# BPF.net
KiCad netlist of a schematic drawn in Altium Designer
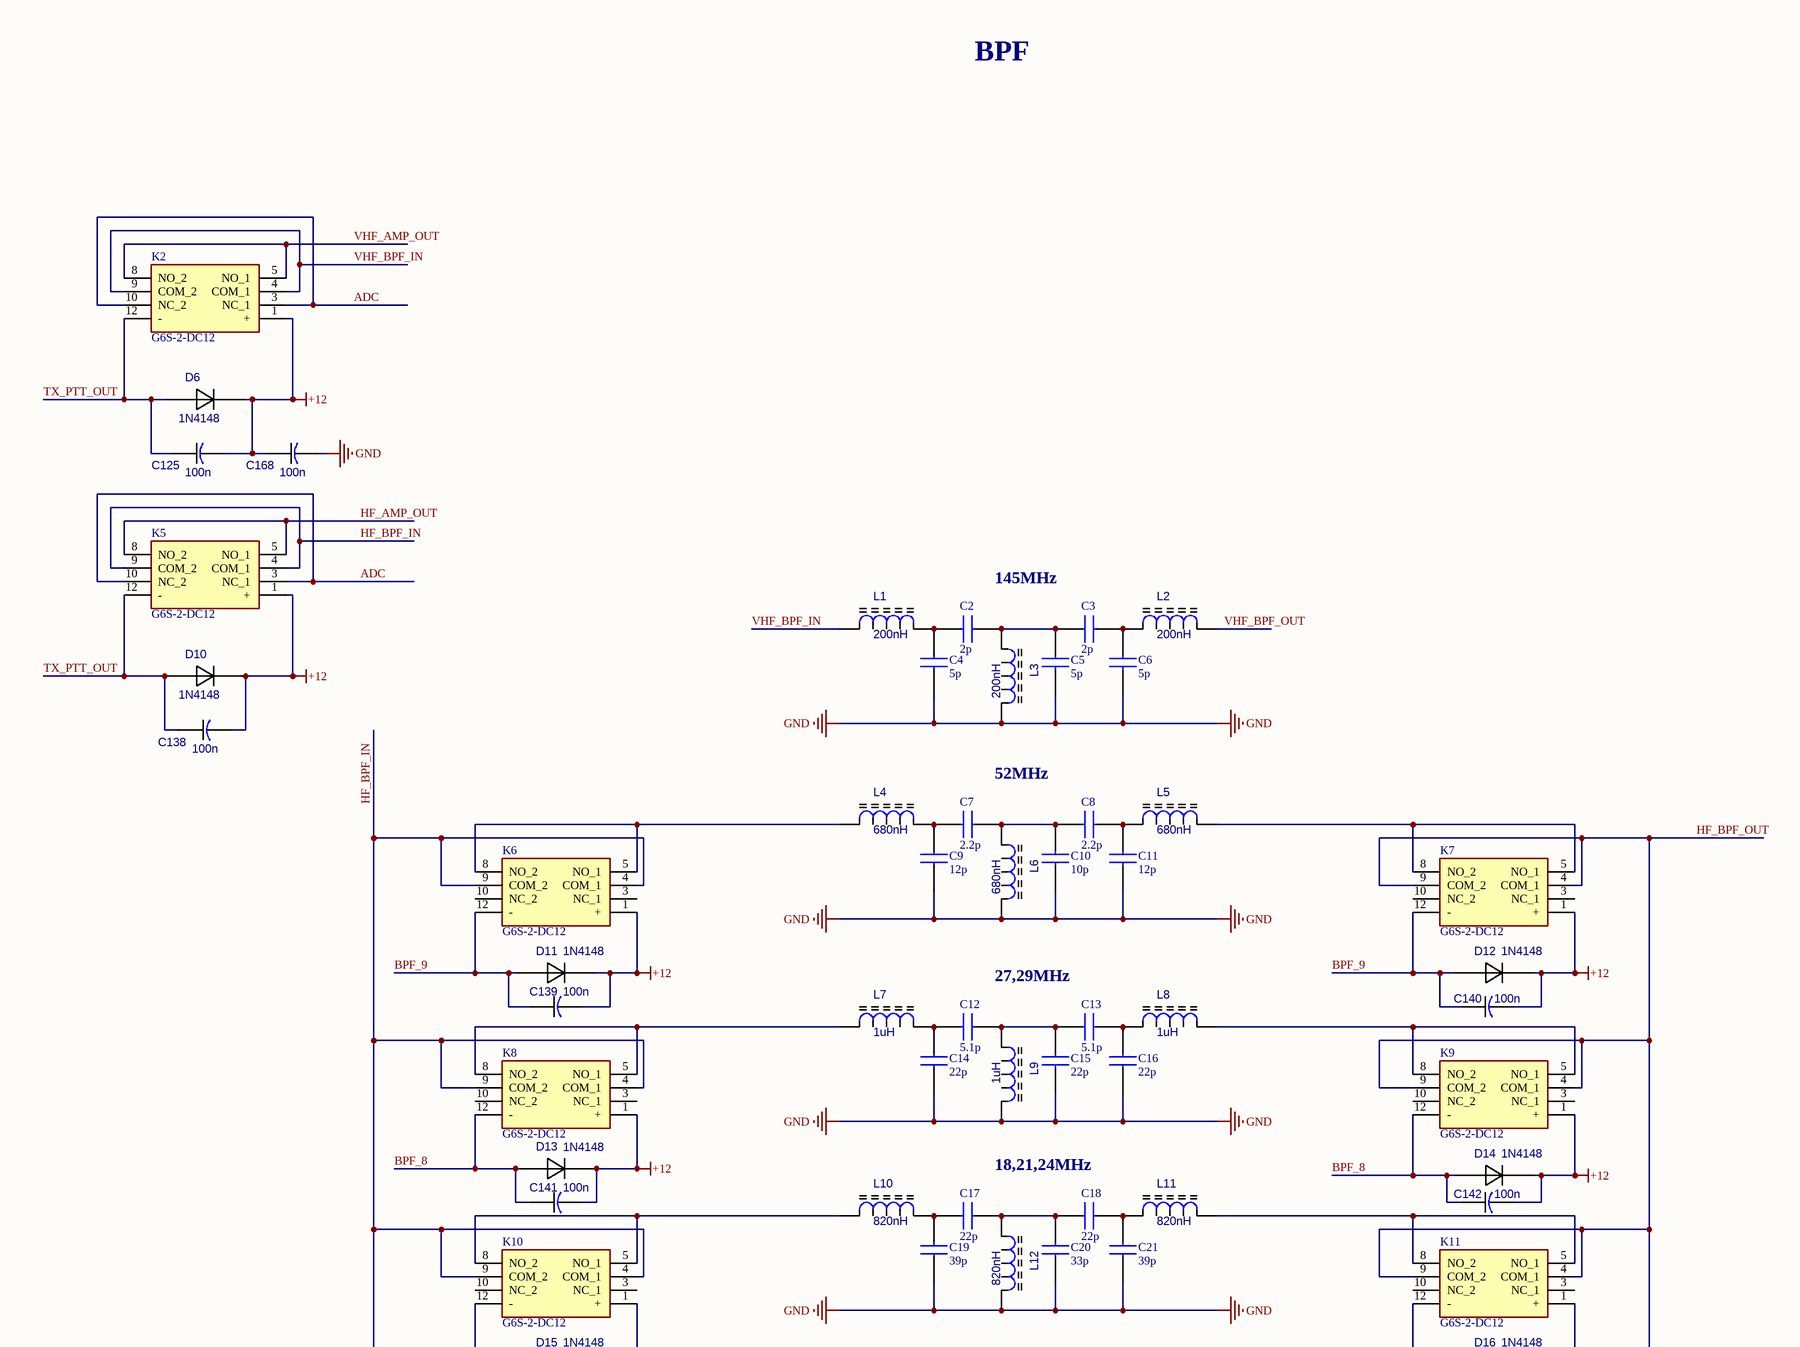
[diagram p0: BPF.SchDoc, top]
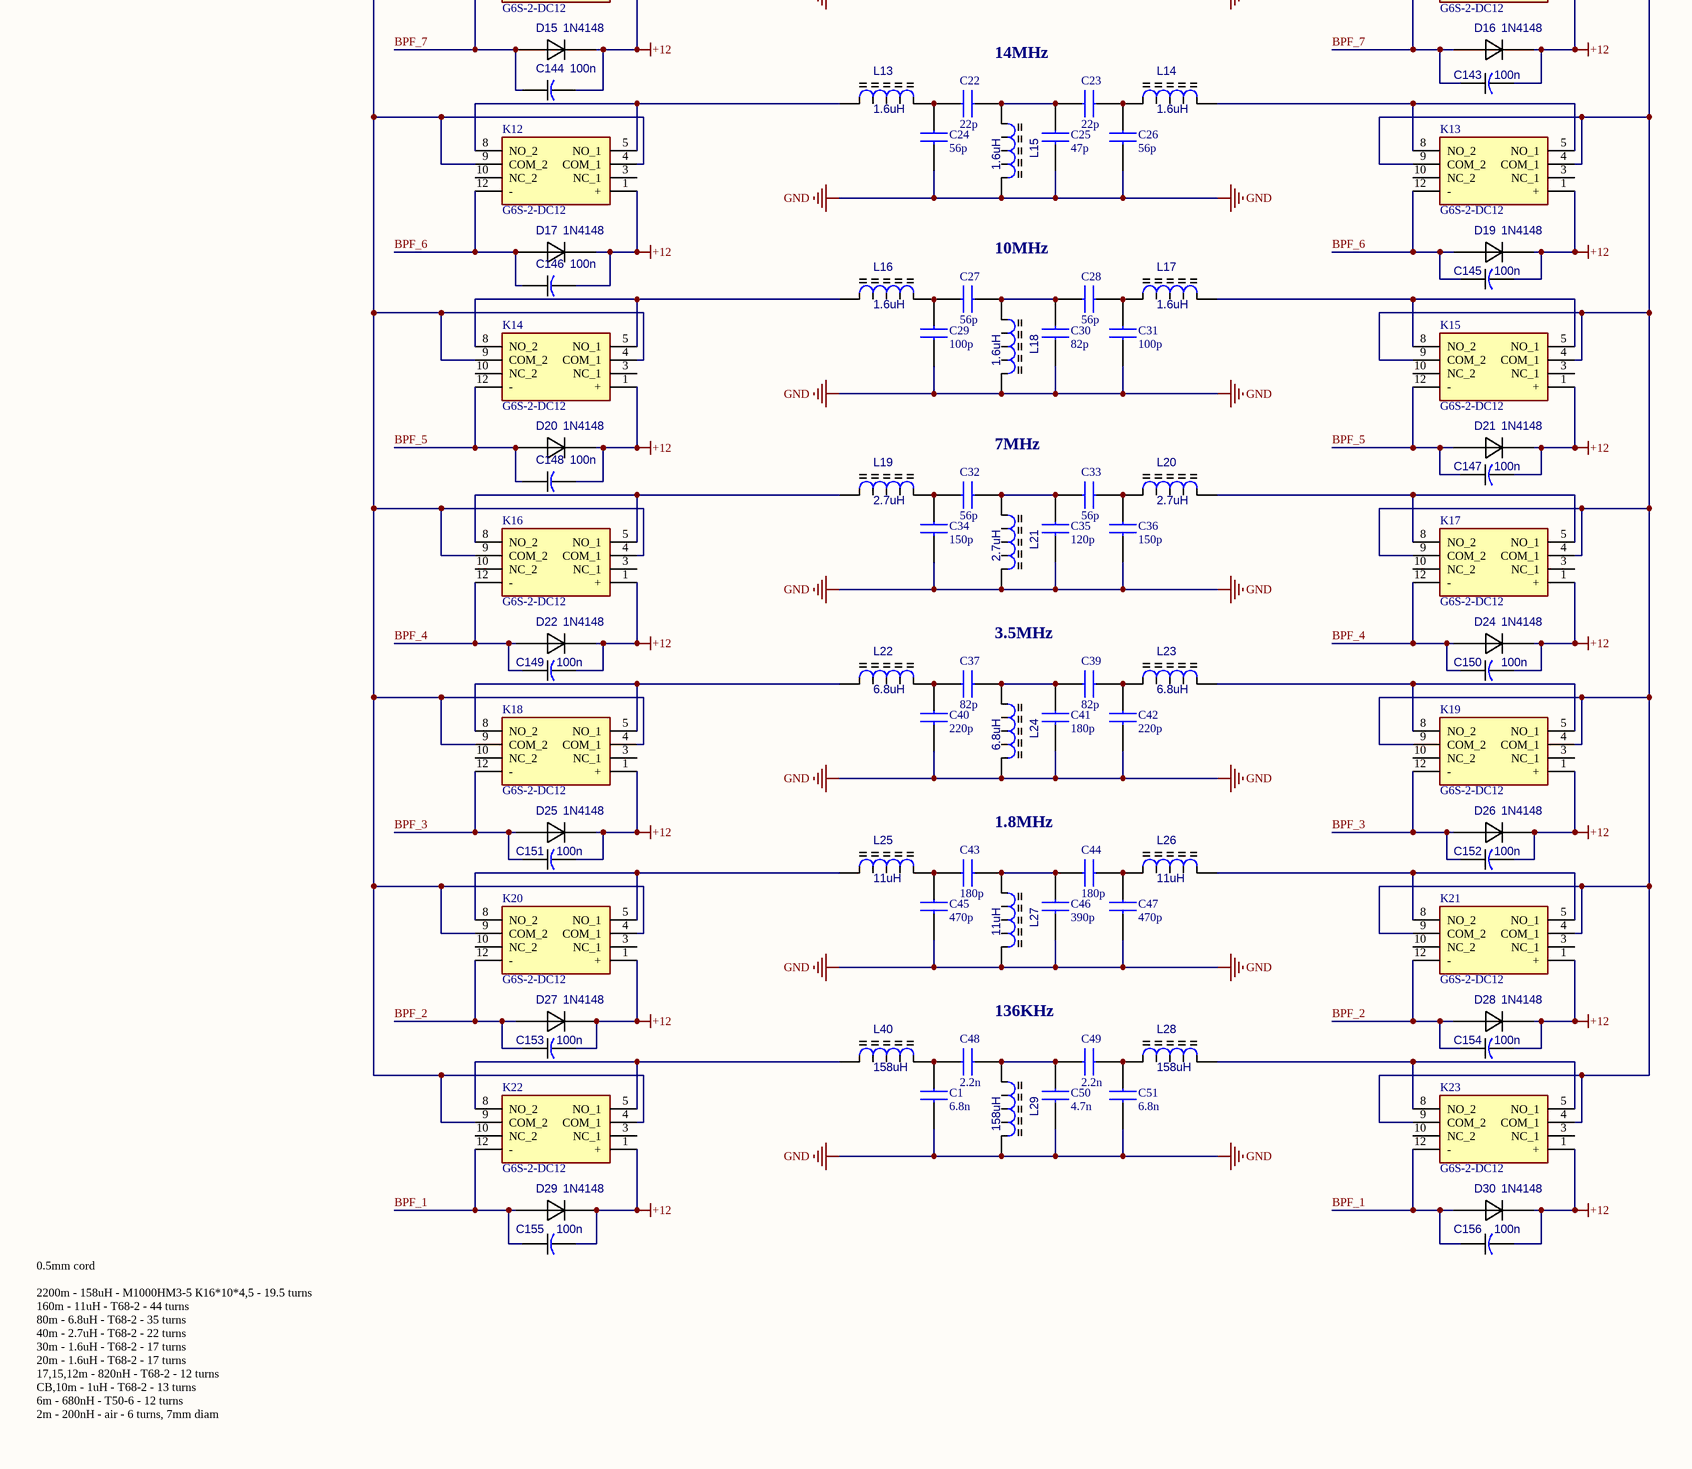
[diagram p1: BPF.SchDoc, bottom]

(export (version "E")
  (design (tool "Eeschema 10.0.6"))
  (components
    (comp (ref "C1")
      (value "6.8n")
      (footprint "CAP_1206")
      (description "Capacitor NP0 HiVolt")
      (fields
        (field (name "MANUFACTURER_PART_NUMBER") "B32620A0682J000")
        (field (name "MOUSER PART NUMBER") "871-B32620A682J")
      )
      (libsource (lib "*") (part "B32620A0682J000"))
    )
    (comp (ref "C2")
      (value "2p")
      (footprint "CAP_1206")
      (description "Capacitor NP0 HiVolt")
      (fields
        (field (name "MANUFACTURER_PART_NUMBER") "B32620A0682J000")
        (field (name "MOUSER PART NUMBER") "871-B32620A682J")
      )
      (libsource (lib "*") (part "B32620A0682J000"))
    )
    (comp (ref "C3")
      (value "2p")
      (footprint "CAP_1206")
      (description "Capacitor NP0 HiVolt")
      (fields
        (field (name "MANUFACTURER_PART_NUMBER") "B32620A0682J000")
        (field (name "MOUSER PART NUMBER") "871-B32620A682J")
      )
      (libsource (lib "*") (part "B32620A0682J000"))
    )
    (comp (ref "C4")
      (value "5p")
      (footprint "CAP_1206")
      (description "Capacitor NP0 HiVolt")
      (fields
        (field (name "MANUFACTURER_PART_NUMBER") "B32620A0682J000")
        (field (name "MOUSER PART NUMBER") "871-B32620A682J")
      )
      (libsource (lib "*") (part "B32620A0682J000"))
    )
    (comp (ref "C5")
      (value "5p")
      (footprint "CAP_1206")
      (description "Capacitor NP0 HiVolt")
      (fields
        (field (name "MANUFACTURER_PART_NUMBER") "B32620A0682J000")
        (field (name "MOUSER PART NUMBER") "871-B32620A682J")
      )
      (libsource (lib "*") (part "B32620A0682J000"))
    )
    (comp (ref "C6")
      (value "5p")
      (footprint "CAP_1206")
      (description "Capacitor NP0 HiVolt")
      (fields
        (field (name "MANUFACTURER_PART_NUMBER") "B32620A0682J000")
        (field (name "MOUSER PART NUMBER") "871-B32620A682J")
      )
      (libsource (lib "*") (part "B32620A0682J000"))
    )
    (comp (ref "C7")
      (value "2.2p")
      (footprint "CAP_1206")
      (description "Capacitor NP0 HiVolt")
      (fields
        (field (name "MANUFACTURER_PART_NUMBER") "B32620A0682J000")
        (field (name "MOUSER PART NUMBER") "871-B32620A682J")
      )
      (libsource (lib "*") (part "B32620A0682J000"))
    )
    (comp (ref "C8")
      (value "2.2p")
      (footprint "CAP_1206")
      (description "Capacitor NP0 HiVolt")
      (fields
        (field (name "MANUFACTURER_PART_NUMBER") "B32620A0682J000")
        (field (name "MOUSER PART NUMBER") "871-B32620A682J")
      )
      (libsource (lib "*") (part "B32620A0682J000"))
    )
    (comp (ref "C9")
      (value "12p")
      (footprint "CAP_1206")
      (description "Capacitor NP0 HiVolt")
      (fields
        (field (name "MANUFACTURER_PART_NUMBER") "B32620A0682J000")
        (field (name "MOUSER PART NUMBER") "871-B32620A682J")
      )
      (libsource (lib "*") (part "B32620A0682J000"))
    )
    (comp (ref "C10")
      (value "10p")
      (footprint "CAP_1206")
      (description "Capacitor NP0 HiVolt")
      (fields
        (field (name "MANUFACTURER_PART_NUMBER") "B32620A0682J000")
        (field (name "MOUSER PART NUMBER") "871-B32620A682J")
      )
      (libsource (lib "*") (part "B32620A0682J000"))
    )
    (comp (ref "C11")
      (value "12p")
      (footprint "CAP_1206")
      (description "Capacitor NP0 HiVolt")
      (fields
        (field (name "MANUFACTURER_PART_NUMBER") "B32620A0682J000")
        (field (name "MOUSER PART NUMBER") "871-B32620A682J")
      )
      (libsource (lib "*") (part "B32620A0682J000"))
    )
    (comp (ref "C12")
      (value "5.1p")
      (footprint "CAP_1206")
      (description "Capacitor NP0 HiVolt")
      (fields
        (field (name "MANUFACTURER_PART_NUMBER") "B32620A0682J000")
        (field (name "MOUSER PART NUMBER") "871-B32620A682J")
      )
      (libsource (lib "*") (part "B32620A0682J000"))
    )
    (comp (ref "C13")
      (value "5.1p")
      (footprint "CAP_1206")
      (description "Capacitor NP0 HiVolt")
      (fields
        (field (name "MANUFACTURER_PART_NUMBER") "B32620A0682J000")
        (field (name "MOUSER PART NUMBER") "871-B32620A682J")
      )
      (libsource (lib "*") (part "B32620A0682J000"))
    )
    (comp (ref "C14")
      (value "22p")
      (footprint "CAP_1206")
      (description "Capacitor NP0 HiVolt")
      (fields
        (field (name "MANUFACTURER_PART_NUMBER") "B32620A0682J000")
        (field (name "MOUSER PART NUMBER") "871-B32620A682J")
      )
      (libsource (lib "*") (part "B32620A0682J000"))
    )
    (comp (ref "C15")
      (value "22p")
      (footprint "CAP_1206")
      (description "Capacitor NP0 HiVolt")
      (fields
        (field (name "MANUFACTURER_PART_NUMBER") "B32620A0682J000")
        (field (name "MOUSER PART NUMBER") "871-B32620A682J")
      )
      (libsource (lib "*") (part "B32620A0682J000"))
    )
    (comp (ref "C16")
      (value "22p")
      (footprint "CAP_1206")
      (description "Capacitor NP0 HiVolt")
      (fields
        (field (name "MANUFACTURER_PART_NUMBER") "B32620A0682J000")
        (field (name "MOUSER PART NUMBER") "871-B32620A682J")
      )
      (libsource (lib "*") (part "B32620A0682J000"))
    )
    (comp (ref "C17")
      (value "22p")
      (footprint "CAP_1206")
      (description "Capacitor NP0 HiVolt")
      (fields
        (field (name "MANUFACTURER_PART_NUMBER") "B32620A0682J000")
        (field (name "MOUSER PART NUMBER") "871-B32620A682J")
      )
      (libsource (lib "*") (part "B32620A0682J000"))
    )
    (comp (ref "C18")
      (value "22p")
      (footprint "CAP_1206")
      (description "Capacitor NP0 HiVolt")
      (fields
        (field (name "MANUFACTURER_PART_NUMBER") "B32620A0682J000")
        (field (name "MOUSER PART NUMBER") "871-B32620A682J")
      )
      (libsource (lib "*") (part "B32620A0682J000"))
    )
    (comp (ref "C19")
      (value "39p")
      (footprint "CAP_1206")
      (description "Capacitor NP0 HiVolt")
      (fields
        (field (name "MANUFACTURER_PART_NUMBER") "B32620A0682J000")
        (field (name "MOUSER PART NUMBER") "871-B32620A682J")
      )
      (libsource (lib "*") (part "B32620A0682J000"))
    )
    (comp (ref "C20")
      (value "33p")
      (footprint "CAP_1206")
      (description "Capacitor NP0 HiVolt")
      (fields
        (field (name "MANUFACTURER_PART_NUMBER") "B32620A0682J000")
        (field (name "MOUSER PART NUMBER") "871-B32620A682J")
      )
      (libsource (lib "*") (part "B32620A0682J000"))
    )
    (comp (ref "C21")
      (value "39p")
      (footprint "CAP_1206")
      (description "Capacitor NP0 HiVolt")
      (fields
        (field (name "MANUFACTURER_PART_NUMBER") "B32620A0682J000")
        (field (name "MOUSER PART NUMBER") "871-B32620A682J")
      )
      (libsource (lib "*") (part "B32620A0682J000"))
    )
    (comp (ref "C22")
      (value "22p")
      (footprint "CAP_1206")
      (description "Capacitor NP0 HiVolt")
      (fields
        (field (name "MANUFACTURER_PART_NUMBER") "B32620A0682J000")
        (field (name "MOUSER PART NUMBER") "871-B32620A682J")
      )
      (libsource (lib "*") (part "B32620A0682J000"))
    )
    (comp (ref "C23")
      (value "22p")
      (footprint "CAP_1206")
      (description "Capacitor NP0 HiVolt")
      (fields
        (field (name "MANUFACTURER_PART_NUMBER") "B32620A0682J000")
        (field (name "MOUSER PART NUMBER") "871-B32620A682J")
      )
      (libsource (lib "*") (part "B32620A0682J000"))
    )
    (comp (ref "C24")
      (value "56p")
      (footprint "CAP_1206")
      (description "Capacitor NP0 HiVolt")
      (fields
        (field (name "MANUFACTURER_PART_NUMBER") "B32620A0682J000")
        (field (name "MOUSER PART NUMBER") "871-B32620A682J")
      )
      (libsource (lib "*") (part "B32620A0682J000"))
    )
    (comp (ref "C25")
      (value "47p")
      (footprint "CAP_1206")
      (description "Capacitor NP0 HiVolt")
      (fields
        (field (name "MANUFACTURER_PART_NUMBER") "B32620A0682J000")
        (field (name "MOUSER PART NUMBER") "871-B32620A682J")
      )
      (libsource (lib "*") (part "B32620A0682J000"))
    )
    (comp (ref "C26")
      (value "56p")
      (footprint "CAP_1206")
      (description "Capacitor NP0 HiVolt")
      (fields
        (field (name "MANUFACTURER_PART_NUMBER") "B32620A0682J000")
        (field (name "MOUSER PART NUMBER") "871-B32620A682J")
      )
      (libsource (lib "*") (part "B32620A0682J000"))
    )
    (comp (ref "C27")
      (value "56p")
      (footprint "CAP_1206")
      (description "Capacitor NP0 HiVolt")
      (fields
        (field (name "MANUFACTURER_PART_NUMBER") "B32620A0682J000")
        (field (name "MOUSER PART NUMBER") "871-B32620A682J")
      )
      (libsource (lib "*") (part "B32620A0682J000"))
    )
    (comp (ref "C28")
      (value "56p")
      (footprint "CAP_1206")
      (description "Capacitor NP0 HiVolt")
      (fields
        (field (name "MANUFACTURER_PART_NUMBER") "B32620A0682J000")
        (field (name "MOUSER PART NUMBER") "871-B32620A682J")
      )
      (libsource (lib "*") (part "B32620A0682J000"))
    )
    (comp (ref "C29")
      (value "100p")
      (footprint "CAP_1206")
      (description "Capacitor NP0 HiVolt")
      (fields
        (field (name "MANUFACTURER_PART_NUMBER") "B32620A0682J000")
        (field (name "MOUSER PART NUMBER") "871-B32620A682J")
      )
      (libsource (lib "*") (part "B32620A0682J000"))
    )
    (comp (ref "C30")
      (value "82p")
      (footprint "CAP_1206")
      (description "Capacitor NP0 HiVolt")
      (fields
        (field (name "MANUFACTURER_PART_NUMBER") "B32620A0682J000")
        (field (name "MOUSER PART NUMBER") "871-B32620A682J")
      )
      (libsource (lib "*") (part "B32620A0682J000"))
    )
    (comp (ref "C31")
      (value "100p")
      (footprint "CAP_1206")
      (description "Capacitor NP0 HiVolt")
      (fields
        (field (name "MANUFACTURER_PART_NUMBER") "B32620A0682J000")
        (field (name "MOUSER PART NUMBER") "871-B32620A682J")
      )
      (libsource (lib "*") (part "B32620A0682J000"))
    )
    (comp (ref "C32")
      (value "56p")
      (footprint "CAP_1206")
      (description "Capacitor NP0 HiVolt")
      (fields
        (field (name "MANUFACTURER_PART_NUMBER") "B32620A0682J000")
        (field (name "MOUSER PART NUMBER") "871-B32620A682J")
      )
      (libsource (lib "*") (part "B32620A0682J000"))
    )
    (comp (ref "C33")
      (value "56p")
      (footprint "CAP_1206")
      (description "Capacitor NP0 HiVolt")
      (fields
        (field (name "MANUFACTURER_PART_NUMBER") "B32620A0682J000")
        (field (name "MOUSER PART NUMBER") "871-B32620A682J")
      )
      (libsource (lib "*") (part "B32620A0682J000"))
    )
    (comp (ref "C34")
      (value "150p")
      (footprint "CAP_1206")
      (description "Capacitor NP0 HiVolt")
      (fields
        (field (name "MANUFACTURER_PART_NUMBER") "B32620A0682J000")
        (field (name "MOUSER PART NUMBER") "871-B32620A682J")
      )
      (libsource (lib "*") (part "B32620A0682J000"))
    )
    (comp (ref "C35")
      (value "120p")
      (footprint "CAP_1206")
      (description "Capacitor NP0 HiVolt")
      (fields
        (field (name "MANUFACTURER_PART_NUMBER") "B32620A0682J000")
        (field (name "MOUSER PART NUMBER") "871-B32620A682J")
      )
      (libsource (lib "*") (part "B32620A0682J000"))
    )
    (comp (ref "C36")
      (value "150p")
      (footprint "CAP_1206")
      (description "Capacitor NP0 HiVolt")
      (fields
        (field (name "MANUFACTURER_PART_NUMBER") "B32620A0682J000")
        (field (name "MOUSER PART NUMBER") "871-B32620A682J")
      )
      (libsource (lib "*") (part "B32620A0682J000"))
    )
    (comp (ref "C37")
      (value "82p")
      (footprint "CAP_1206")
      (description "Capacitor NP0 HiVolt")
      (fields
        (field (name "MANUFACTURER_PART_NUMBER") "B32620A0682J000")
        (field (name "MOUSER PART NUMBER") "871-B32620A682J")
      )
      (libsource (lib "*") (part "B32620A0682J000"))
    )
    (comp (ref "C39")
      (value "82p")
      (footprint "CAP_1206")
      (description "Capacitor NP0 HiVolt")
      (fields
        (field (name "MANUFACTURER_PART_NUMBER") "B32620A0682J000")
        (field (name "MOUSER PART NUMBER") "871-B32620A682J")
      )
      (libsource (lib "*") (part "B32620A0682J000"))
    )
    (comp (ref "C40")
      (value "220p")
      (footprint "CAP_1206")
      (description "Capacitor NP0 HiVolt")
      (fields
        (field (name "MANUFACTURER_PART_NUMBER") "B32620A0682J000")
        (field (name "MOUSER PART NUMBER") "871-B32620A682J")
      )
      (libsource (lib "*") (part "B32620A0682J000"))
    )
    (comp (ref "C41")
      (value "180p")
      (footprint "CAP_1206")
      (description "Capacitor NP0 HiVolt")
      (fields
        (field (name "MANUFACTURER_PART_NUMBER") "B32620A0682J000")
        (field (name "MOUSER PART NUMBER") "871-B32620A682J")
      )
      (libsource (lib "*") (part "B32620A0682J000"))
    )
    (comp (ref "C42")
      (value "220p")
      (footprint "CAP_1206")
      (description "Capacitor NP0 HiVolt")
      (fields
        (field (name "MANUFACTURER_PART_NUMBER") "B32620A0682J000")
        (field (name "MOUSER PART NUMBER") "871-B32620A682J")
      )
      (libsource (lib "*") (part "B32620A0682J000"))
    )
    (comp (ref "C43")
      (value "180p")
      (footprint "CAP_1206")
      (description "Capacitor NP0 HiVolt")
      (fields
        (field (name "MANUFACTURER_PART_NUMBER") "B32620A0682J000")
        (field (name "MOUSER PART NUMBER") "871-B32620A682J")
      )
      (libsource (lib "*") (part "B32620A0682J000"))
    )
    (comp (ref "C44")
      (value "180p")
      (footprint "CAP_1206")
      (description "Capacitor NP0 HiVolt")
      (fields
        (field (name "MANUFACTURER_PART_NUMBER") "B32620A0682J000")
        (field (name "MOUSER PART NUMBER") "871-B32620A682J")
      )
      (libsource (lib "*") (part "B32620A0682J000"))
    )
    (comp (ref "C45")
      (value "470p")
      (footprint "CAP_1206")
      (description "Capacitor NP0 HiVolt")
      (fields
        (field (name "MANUFACTURER_PART_NUMBER") "B32620A0682J000")
        (field (name "MOUSER PART NUMBER") "871-B32620A682J")
      )
      (libsource (lib "*") (part "B32620A0682J000"))
    )
    (comp (ref "C46")
      (value "390p")
      (footprint "CAP_1206")
      (description "Capacitor NP0 HiVolt")
      (fields
        (field (name "MANUFACTURER_PART_NUMBER") "B32620A0682J000")
        (field (name "MOUSER PART NUMBER") "871-B32620A682J")
      )
      (libsource (lib "*") (part "B32620A0682J000"))
    )
    (comp (ref "C47")
      (value "470p")
      (footprint "CAP_1206")
      (description "Capacitor NP0 HiVolt")
      (fields
        (field (name "MANUFACTURER_PART_NUMBER") "B32620A0682J000")
        (field (name "MOUSER PART NUMBER") "871-B32620A682J")
      )
      (libsource (lib "*") (part "B32620A0682J000"))
    )
    (comp (ref "C48")
      (value "2.2n")
      (footprint "CAP_1206")
      (description "Capacitor NP0 HiVolt")
      (fields
        (field (name "MANUFACTURER_PART_NUMBER") "B32620A0682J000")
        (field (name "MOUSER PART NUMBER") "871-B32620A682J")
      )
      (libsource (lib "*") (part "B32620A0682J000"))
    )
    (comp (ref "C49")
      (value "2.2n")
      (footprint "CAP_1206")
      (description "Capacitor NP0 HiVolt")
      (fields
        (field (name "MANUFACTURER_PART_NUMBER") "B32620A0682J000")
        (field (name "MOUSER PART NUMBER") "871-B32620A682J")
      )
      (libsource (lib "*") (part "B32620A0682J000"))
    )
    (comp (ref "C50")
      (value "4.7n")
      (footprint "CAP_1206")
      (description "Capacitor NP0 HiVolt")
      (fields
        (field (name "MANUFACTURER_PART_NUMBER") "B32620A0682J000")
        (field (name "MOUSER PART NUMBER") "871-B32620A682J")
      )
      (libsource (lib "*") (part "B32620A0682J000"))
    )
    (comp (ref "C51")
      (value "6.8n")
      (footprint "CAP_1206")
      (description "Capacitor NP0 HiVolt")
      (fields
        (field (name "MANUFACTURER_PART_NUMBER") "B32620A0682J000")
        (field (name "MOUSER PART NUMBER") "871-B32620A682J")
      )
      (libsource (lib "*") (part "B32620A0682J000"))
    )
    (comp (ref "C125")
      (value "100n")
      (footprint "CAP_0805")
      (description "CAP_0805")
      (libsource (lib "*") (part "CAP_0805"))
    )
    (comp (ref "C138")
      (value "100n")
      (footprint "CAP_0805")
      (description "CAP_0805")
      (libsource (lib "*") (part "CAP_0805"))
    )
    (comp (ref "C139")
      (value "100n")
      (footprint "CAP_0805")
      (description "CAP_0805")
      (libsource (lib "*") (part "CAP_0805"))
    )
    (comp (ref "C140")
      (value "100n")
      (footprint "CAP_0805")
      (description "CAP_0805")
      (libsource (lib "*") (part "CAP_0805"))
    )
    (comp (ref "C141")
      (value "100n")
      (footprint "CAP_0805")
      (description "CAP_0805")
      (libsource (lib "*") (part "CAP_0805"))
    )
    (comp (ref "C142")
      (value "100n")
      (footprint "CAP_0805")
      (description "CAP_0805")
      (libsource (lib "*") (part "CAP_0805"))
    )
    (comp (ref "C143")
      (value "100n")
      (footprint "CAP_0805")
      (description "CAP_0805")
      (libsource (lib "*") (part "CAP_0805"))
    )
    (comp (ref "C144")
      (value "100n")
      (footprint "CAP_0805")
      (description "CAP_0805")
      (libsource (lib "*") (part "CAP_0805"))
    )
    (comp (ref "C145")
      (value "100n")
      (footprint "CAP_0805")
      (description "CAP_0805")
      (libsource (lib "*") (part "CAP_0805"))
    )
    (comp (ref "C146")
      (value "100n")
      (footprint "CAP_0805")
      (description "CAP_0805")
      (libsource (lib "*") (part "CAP_0805"))
    )
    (comp (ref "C147")
      (value "100n")
      (footprint "CAP_0805")
      (description "CAP_0805")
      (libsource (lib "*") (part "CAP_0805"))
    )
    (comp (ref "C148")
      (value "100n")
      (footprint "CAP_0805")
      (description "CAP_0805")
      (libsource (lib "*") (part "CAP_0805"))
    )
    (comp (ref "C149")
      (value "100n")
      (footprint "CAP_0805")
      (description "CAP_0805")
      (libsource (lib "*") (part "CAP_0805"))
    )
    (comp (ref "C150")
      (value "100n")
      (footprint "CAP_0805")
      (description "CAP_0805")
      (libsource (lib "*") (part "CAP_0805"))
    )
    (comp (ref "C151")
      (value "100n")
      (footprint "CAP_0805")
      (description "CAP_0805")
      (libsource (lib "*") (part "CAP_0805"))
    )
    (comp (ref "C152")
      (value "100n")
      (footprint "CAP_0805")
      (description "CAP_0805")
      (libsource (lib "*") (part "CAP_0805"))
    )
    (comp (ref "C153")
      (value "100n")
      (footprint "CAP_0805")
      (description "CAP_0805")
      (libsource (lib "*") (part "CAP_0805"))
    )
    (comp (ref "C154")
      (value "100n")
      (footprint "CAP_0805")
      (description "CAP_0805")
      (libsource (lib "*") (part "CAP_0805"))
    )
    (comp (ref "C155")
      (value "100n")
      (footprint "CAP_0805")
      (description "CAP_0805")
      (libsource (lib "*") (part "CAP_0805"))
    )
    (comp (ref "C156")
      (value "100n")
      (footprint "CAP_0805")
      (description "CAP_0805")
      (libsource (lib "*") (part "CAP_0805"))
    )
    (comp (ref "C168")
      (value "100n")
      (footprint "CAP_0805")
      (description "CAP_0805")
      (libsource (lib "*") (part "CAP_0805"))
    )
    (comp (ref "D6") (value "1N4148") (footprint "SS14") (libsource (lib "RF-UNIT-BIG") (part "1N4148")))
    (comp (ref "D10") (value "1N4148") (footprint "SS14") (libsource (lib "RF-UNIT-BIG") (part "1N4148")))
    (comp (ref "D11") (value "1N4148") (footprint "SS14") (libsource (lib "RF-UNIT-BIG") (part "1N4148")))
    (comp (ref "D12") (value "1N4148") (footprint "SS14") (libsource (lib "RF-UNIT-BIG") (part "1N4148")))
    (comp (ref "D13") (value "1N4148") (footprint "SS14") (libsource (lib "RF-UNIT-BIG") (part "1N4148")))
    (comp (ref "D14") (value "1N4148") (footprint "SS14") (libsource (lib "RF-UNIT-BIG") (part "1N4148")))
    (comp (ref "D15") (value "1N4148") (footprint "SS14") (libsource (lib "RF-UNIT-BIG") (part "1N4148")))
    (comp (ref "D16") (value "1N4148") (footprint "SS14") (libsource (lib "RF-UNIT-BIG") (part "1N4148")))
    (comp (ref "D17") (value "1N4148") (footprint "SS14") (libsource (lib "RF-UNIT-BIG") (part "1N4148")))
    (comp (ref "D19") (value "1N4148") (footprint "SS14") (libsource (lib "RF-UNIT-BIG") (part "1N4148")))
    (comp (ref "D20") (value "1N4148") (footprint "SS14") (libsource (lib "RF-UNIT-BIG") (part "1N4148")))
    (comp (ref "D21") (value "1N4148") (footprint "SS14") (libsource (lib "RF-UNIT-BIG") (part "1N4148")))
    (comp (ref "D22") (value "1N4148") (footprint "SS14") (libsource (lib "RF-UNIT-BIG") (part "1N4148")))
    (comp (ref "D24") (value "1N4148") (footprint "SS14") (libsource (lib "RF-UNIT-BIG") (part "1N4148")))
    (comp (ref "D25") (value "1N4148") (footprint "SS14") (libsource (lib "RF-UNIT-BIG") (part "1N4148")))
    (comp (ref "D26") (value "1N4148") (footprint "SS14") (libsource (lib "RF-UNIT-BIG") (part "1N4148")))
    (comp (ref "D27") (value "1N4148") (footprint "SS14") (libsource (lib "RF-UNIT-BIG") (part "1N4148")))
    (comp (ref "D28") (value "1N4148") (footprint "SS14") (libsource (lib "RF-UNIT-BIG") (part "1N4148")))
    (comp (ref "D29") (value "1N4148") (footprint "SS14") (libsource (lib "RF-UNIT-BIG") (part "1N4148")))
    (comp (ref "D30") (value "1N4148") (footprint "SS14") (libsource (lib "RF-UNIT-BIG") (part "1N4148")))
    (comp (ref "K2")
      (value "G6S-2-DC12")
      (footprint "SamacSys:G6S2DC12")
      (description "Relay or Contactor")
      (fields (field (name "MOUSER PART NUMBER") "653-G6S-2-DC12A"))
      (libsource (lib "*") (part "G6S-2-DC12"))
    )
    (comp (ref "K5")
      (value "G6S-2-DC12")
      (footprint "SamacSys:G6S2DC12")
      (description "Relay or Contactor")
      (fields (field (name "MOUSER PART NUMBER") "653-G6S-2-DC12A"))
      (libsource (lib "*") (part "G6S-2-DC12"))
    )
    (comp (ref "K6")
      (value "G6S-2-DC12")
      (footprint "SamacSys:G6S2DC12")
      (description "Relay or Contactor")
      (fields (field (name "MOUSER PART NUMBER") "653-G6S-2-DC12A"))
      (libsource (lib "*") (part "G6S-2-DC12"))
    )
    (comp (ref "K7")
      (value "G6S-2-DC12")
      (footprint "SamacSys:G6S2DC12")
      (description "Relay or Contactor")
      (fields (field (name "MOUSER PART NUMBER") "653-G6S-2-DC12A"))
      (libsource (lib "*") (part "G6S-2-DC12"))
    )
    (comp (ref "K8")
      (value "G6S-2-DC12")
      (footprint "SamacSys:G6S2DC12")
      (description "Relay or Contactor")
      (fields (field (name "MOUSER PART NUMBER") "653-G6S-2-DC12A"))
      (libsource (lib "*") (part "G6S-2-DC12"))
    )
    (comp (ref "K9")
      (value "G6S-2-DC12")
      (footprint "SamacSys:G6S2DC12")
      (description "Relay or Contactor")
      (fields (field (name "MOUSER PART NUMBER") "653-G6S-2-DC12A"))
      (libsource (lib "*") (part "G6S-2-DC12"))
    )
    (comp (ref "K10")
      (value "G6S-2-DC12")
      (footprint "SamacSys:G6S2DC12")
      (description "Relay or Contactor")
      (fields (field (name "MOUSER PART NUMBER") "653-G6S-2-DC12A"))
      (libsource (lib "*") (part "G6S-2-DC12"))
    )
    (comp (ref "K11")
      (value "G6S-2-DC12")
      (footprint "SamacSys:G6S2DC12")
      (description "Relay or Contactor")
      (fields (field (name "MOUSER PART NUMBER") "653-G6S-2-DC12A"))
      (libsource (lib "*") (part "G6S-2-DC12"))
    )
    (comp (ref "K12")
      (value "G6S-2-DC12")
      (footprint "SamacSys:G6S2DC12")
      (description "Relay or Contactor")
      (fields (field (name "MOUSER PART NUMBER") "653-G6S-2-DC12A"))
      (libsource (lib "*") (part "G6S-2-DC12"))
    )
    (comp (ref "K13")
      (value "G6S-2-DC12")
      (footprint "SamacSys:G6S2DC12")
      (description "Relay or Contactor")
      (fields (field (name "MOUSER PART NUMBER") "653-G6S-2-DC12A"))
      (libsource (lib "*") (part "G6S-2-DC12"))
    )
    (comp (ref "K14")
      (value "G6S-2-DC12")
      (footprint "SamacSys:G6S2DC12")
      (description "Relay or Contactor")
      (fields (field (name "MOUSER PART NUMBER") "653-G6S-2-DC12A"))
      (libsource (lib "*") (part "G6S-2-DC12"))
    )
    (comp (ref "K15")
      (value "G6S-2-DC12")
      (footprint "SamacSys:G6S2DC12")
      (description "Relay or Contactor")
      (fields (field (name "MOUSER PART NUMBER") "653-G6S-2-DC12A"))
      (libsource (lib "*") (part "G6S-2-DC12"))
    )
    (comp (ref "K16")
      (value "G6S-2-DC12")
      (footprint "SamacSys:G6S2DC12")
      (description "Relay or Contactor")
      (fields (field (name "MOUSER PART NUMBER") "653-G6S-2-DC12A"))
      (libsource (lib "*") (part "G6S-2-DC12"))
    )
    (comp (ref "K17")
      (value "G6S-2-DC12")
      (footprint "SamacSys:G6S2DC12")
      (description "Relay or Contactor")
      (fields (field (name "MOUSER PART NUMBER") "653-G6S-2-DC12A"))
      (libsource (lib "*") (part "G6S-2-DC12"))
    )
    (comp (ref "K18")
      (value "G6S-2-DC12")
      (footprint "SamacSys:G6S2DC12")
      (description "Relay or Contactor")
      (fields (field (name "MOUSER PART NUMBER") "653-G6S-2-DC12A"))
      (libsource (lib "*") (part "G6S-2-DC12"))
    )
    (comp (ref "K19")
      (value "G6S-2-DC12")
      (footprint "SamacSys:G6S2DC12")
      (description "Relay or Contactor")
      (fields (field (name "MOUSER PART NUMBER") "653-G6S-2-DC12A"))
      (libsource (lib "*") (part "G6S-2-DC12"))
    )
    (comp (ref "K20")
      (value "G6S-2-DC12")
      (footprint "SamacSys:G6S2DC12")
      (description "Relay or Contactor")
      (fields (field (name "MOUSER PART NUMBER") "653-G6S-2-DC12A"))
      (libsource (lib "*") (part "G6S-2-DC12"))
    )
    (comp (ref "K21")
      (value "G6S-2-DC12")
      (footprint "SamacSys:G6S2DC12")
      (description "Relay or Contactor")
      (fields (field (name "MOUSER PART NUMBER") "653-G6S-2-DC12A"))
      (libsource (lib "*") (part "G6S-2-DC12"))
    )
    (comp (ref "K22")
      (value "G6S-2-DC12")
      (footprint "SamacSys:G6S2DC12")
      (description "Relay or Contactor")
      (fields (field (name "MOUSER PART NUMBER") "653-G6S-2-DC12A"))
      (libsource (lib "*") (part "G6S-2-DC12"))
    )
    (comp (ref "K23")
      (value "G6S-2-DC12")
      (footprint "SamacSys:G6S2DC12")
      (description "Relay or Contactor")
      (fields (field (name "MOUSER PART NUMBER") "653-G6S-2-DC12A"))
      (libsource (lib "*") (part "G6S-2-DC12"))
    )
    (comp (ref "L1")
      (value "200nH")
      (footprint "IND_FERRITE_CORE_1")
      (description "Inductor")
      (libsource (lib "*") (part "IND_FERRITE_CORE"))
    )
    (comp (ref "L2")
      (value "200nH")
      (footprint "IND_FERRITE_CORE_1")
      (description "Inductor")
      (libsource (lib "*") (part "IND_FERRITE_CORE"))
    )
    (comp (ref "L3")
      (value "200nH")
      (footprint "IND_FERRITE_CORE_1")
      (description "Inductor")
      (libsource (lib "*") (part "IND_FERRITE_CORE"))
    )
    (comp (ref "L4")
      (value "680nH")
      (footprint "IND_FERRITE_CORE_1")
      (description "Inductor")
      (libsource (lib "*") (part "IND_FERRITE_CORE"))
    )
    (comp (ref "L5")
      (value "680nH")
      (footprint "IND_FERRITE_CORE_1")
      (description "Inductor")
      (libsource (lib "*") (part "IND_FERRITE_CORE"))
    )
    (comp (ref "L6")
      (value "680nH")
      (footprint "IND_FERRITE_CORE_1")
      (description "Inductor")
      (libsource (lib "*") (part "IND_FERRITE_CORE"))
    )
    (comp (ref "L7")
      (value "1uH")
      (footprint "IND_FERRITE_CORE_1")
      (description "Inductor")
      (libsource (lib "*") (part "IND_FERRITE_CORE"))
    )
    (comp (ref "L8")
      (value "1uH")
      (footprint "IND_FERRITE_CORE_1")
      (description "Inductor")
      (libsource (lib "*") (part "IND_FERRITE_CORE"))
    )
    (comp (ref "L9")
      (value "1uH")
      (footprint "IND_FERRITE_CORE_1")
      (description "Inductor")
      (libsource (lib "*") (part "IND_FERRITE_CORE"))
    )
    (comp (ref "L10")
      (value "820nH")
      (footprint "IND_FERRITE_CORE_1")
      (description "Inductor")
      (libsource (lib "*") (part "IND_FERRITE_CORE"))
    )
    (comp (ref "L11")
      (value "820nH")
      (footprint "IND_FERRITE_CORE_1")
      (description "Inductor")
      (libsource (lib "*") (part "IND_FERRITE_CORE"))
    )
    (comp (ref "L12")
      (value "820nH")
      (footprint "IND_FERRITE_CORE_1")
      (description "Inductor")
      (libsource (lib "*") (part "IND_FERRITE_CORE"))
    )
    (comp (ref "L13")
      (value "1.6uH")
      (footprint "IND_FERRITE_CORE_1")
      (description "Inductor")
      (libsource (lib "*") (part "IND_FERRITE_CORE"))
    )
    (comp (ref "L14")
      (value "1.6uH")
      (footprint "IND_FERRITE_CORE_1")
      (description "Inductor")
      (libsource (lib "*") (part "IND_FERRITE_CORE"))
    )
    (comp (ref "L15")
      (value "1.6uH")
      (footprint "IND_FERRITE_CORE_1")
      (description "Inductor")
      (libsource (lib "*") (part "IND_FERRITE_CORE"))
    )
    (comp (ref "L16")
      (value "1.6uH")
      (footprint "IND_FERRITE_CORE_1")
      (description "Inductor")
      (libsource (lib "*") (part "IND_FERRITE_CORE"))
    )
    (comp (ref "L17")
      (value "1.6uH")
      (footprint "IND_FERRITE_CORE_1")
      (description "Inductor")
      (libsource (lib "*") (part "IND_FERRITE_CORE"))
    )
    (comp (ref "L18")
      (value "1.6uH")
      (footprint "IND_FERRITE_CORE_1")
      (description "Inductor")
      (libsource (lib "*") (part "IND_FERRITE_CORE"))
    )
    (comp (ref "L19")
      (value "2.7uH")
      (footprint "IND_FERRITE_CORE_1")
      (description "Inductor")
      (libsource (lib "*") (part "IND_FERRITE_CORE"))
    )
    (comp (ref "L20")
      (value "2.7uH")
      (footprint "IND_FERRITE_CORE_1")
      (description "Inductor")
      (libsource (lib "*") (part "IND_FERRITE_CORE"))
    )
    (comp (ref "L21")
      (value "2.7uH")
      (footprint "IND_FERRITE_CORE_1")
      (description "Inductor")
      (libsource (lib "*") (part "IND_FERRITE_CORE"))
    )
    (comp (ref "L22")
      (value "6.8uH")
      (footprint "IND_FERRITE_CORE_1")
      (description "Inductor")
      (libsource (lib "*") (part "IND_FERRITE_CORE"))
    )
    (comp (ref "L23")
      (value "6.8uH")
      (footprint "IND_FERRITE_CORE_1")
      (description "Inductor")
      (libsource (lib "*") (part "IND_FERRITE_CORE"))
    )
    (comp (ref "L24")
      (value "6.8uH")
      (footprint "IND_FERRITE_CORE_1")
      (description "Inductor")
      (libsource (lib "*") (part "IND_FERRITE_CORE"))
    )
    (comp (ref "L25")
      (value "11uH")
      (footprint "IND_FERRITE_CORE_1")
      (description "Inductor")
      (libsource (lib "*") (part "IND_FERRITE_CORE"))
    )
    (comp (ref "L26")
      (value "11uH")
      (footprint "IND_FERRITE_CORE_1")
      (description "Inductor")
      (libsource (lib "*") (part "IND_FERRITE_CORE"))
    )
    (comp (ref "L27")
      (value "11uH")
      (footprint "IND_FERRITE_CORE_1")
      (description "Inductor")
      (libsource (lib "*") (part "IND_FERRITE_CORE"))
    )
    (comp (ref "L28")
      (value "158uH")
      (footprint "IND_FERRITE_CORE_1")
      (description "Inductor")
      (libsource (lib "*") (part "IND_FERRITE_CORE"))
    )
    (comp (ref "L29")
      (value "158uH")
      (footprint "IND_FERRITE_CORE_1")
      (description "Inductor")
      (libsource (lib "*") (part "IND_FERRITE_CORE"))
    )
    (comp (ref "L40")
      (value "158uH")
      (footprint "IND_FERRITE_CORE_1")
      (description "Inductor")
      (libsource (lib "*") (part "IND_FERRITE_CORE"))
    )
  )
  (nets
    (net (code "1") (name "+12") (class "Default")
      (node (ref "C125") (pin "2") (pinfunction "2_2") (pintype "passive"))
      (node (ref "C138") (pin "2") (pinfunction "2_2") (pintype "passive"))
      (node (ref "C139") (pin "2") (pinfunction "2_2") (pintype "passive"))
      (node (ref "C140") (pin "2") (pinfunction "2_2") (pintype "passive"))
      (node (ref "C141") (pin "2") (pinfunction "2_2") (pintype "passive"))
      (node (ref "C142") (pin "2") (pinfunction "2_2") (pintype "passive"))
      (node (ref "C143") (pin "2") (pinfunction "2_2") (pintype "passive"))
      (node (ref "C144") (pin "2") (pinfunction "2_2") (pintype "passive"))
      (node (ref "C145") (pin "2") (pinfunction "2_2") (pintype "passive"))
      (node (ref "C146") (pin "2") (pinfunction "2_2") (pintype "passive"))
      (node (ref "C147") (pin "2") (pinfunction "2_2") (pintype "passive"))
      (node (ref "C148") (pin "2") (pinfunction "2_2") (pintype "passive"))
      (node (ref "C149") (pin "2") (pinfunction "2_2") (pintype "passive"))
      (node (ref "C150") (pin "2") (pinfunction "2_2") (pintype "passive"))
      (node (ref "C151") (pin "2") (pinfunction "2_2") (pintype "passive"))
      (node (ref "C152") (pin "2") (pinfunction "2_2") (pintype "passive"))
      (node (ref "C153") (pin "2") (pinfunction "2_2") (pintype "passive"))
      (node (ref "C154") (pin "2") (pinfunction "2_2") (pintype "passive"))
      (node (ref "C155") (pin "2") (pinfunction "2_2") (pintype "passive"))
      (node (ref "C156") (pin "2") (pinfunction "2_2") (pintype "passive"))
      (node (ref "C168") (pin "1") (pinfunction "1_1") (pintype "passive"))
      (node (ref "D10") (pin "1") (pinfunction "K_1") (pintype "passive"))
      (node (ref "D11") (pin "1") (pinfunction "K_1") (pintype "passive"))
      (node (ref "D12") (pin "1") (pinfunction "K_1") (pintype "passive"))
      (node (ref "D13") (pin "1") (pinfunction "K_1") (pintype "passive"))
      (node (ref "D14") (pin "1") (pinfunction "K_1") (pintype "passive"))
      (node (ref "D15") (pin "1") (pinfunction "K_1") (pintype "passive"))
      (node (ref "D16") (pin "1") (pinfunction "K_1") (pintype "passive"))
      (node (ref "D17") (pin "1") (pinfunction "K_1") (pintype "passive"))
      (node (ref "D19") (pin "1") (pinfunction "K_1") (pintype "passive"))
      (node (ref "D20") (pin "1") (pinfunction "K_1") (pintype "passive"))
      (node (ref "D21") (pin "1") (pinfunction "K_1") (pintype "passive"))
      (node (ref "D22") (pin "1") (pinfunction "K_1") (pintype "passive"))
      (node (ref "D24") (pin "1") (pinfunction "K_1") (pintype "passive"))
      (node (ref "D25") (pin "1") (pinfunction "K_1") (pintype "passive"))
      (node (ref "D26") (pin "1") (pinfunction "K_1") (pintype "passive"))
      (node (ref "D27") (pin "1") (pinfunction "K_1") (pintype "passive"))
      (node (ref "D28") (pin "1") (pinfunction "K_1") (pintype "passive"))
      (node (ref "D29") (pin "1") (pinfunction "K_1") (pintype "passive"))
      (node (ref "D30") (pin "1") (pinfunction "K_1") (pintype "passive"))
      (node (ref "D6") (pin "1") (pinfunction "K_1") (pintype "passive"))
      (node (ref "K10") (pin "1") (pinfunction "+_1") (pintype "passive"))
      (node (ref "K11") (pin "1") (pinfunction "+_1") (pintype "passive"))
      (node (ref "K12") (pin "1") (pinfunction "+_1") (pintype "passive"))
      (node (ref "K13") (pin "1") (pinfunction "+_1") (pintype "passive"))
      (node (ref "K14") (pin "1") (pinfunction "+_1") (pintype "passive"))
      (node (ref "K15") (pin "1") (pinfunction "+_1") (pintype "passive"))
      (node (ref "K16") (pin "1") (pinfunction "+_1") (pintype "passive"))
      (node (ref "K17") (pin "1") (pinfunction "+_1") (pintype "passive"))
      (node (ref "K18") (pin "1") (pinfunction "+_1") (pintype "passive"))
      (node (ref "K19") (pin "1") (pinfunction "+_1") (pintype "passive"))
      (node (ref "K2") (pin "1") (pinfunction "+_1") (pintype "passive"))
      (node (ref "K20") (pin "1") (pinfunction "+_1") (pintype "passive"))
      (node (ref "K21") (pin "1") (pinfunction "+_1") (pintype "passive"))
      (node (ref "K22") (pin "1") (pinfunction "+_1") (pintype "passive"))
      (node (ref "K23") (pin "1") (pinfunction "+_1") (pintype "passive"))
      (node (ref "K5") (pin "1") (pinfunction "+_1") (pintype "passive"))
      (node (ref "K6") (pin "1") (pinfunction "+_1") (pintype "passive"))
      (node (ref "K7") (pin "1") (pinfunction "+_1") (pintype "passive"))
      (node (ref "K8") (pin "1") (pinfunction "+_1") (pintype "passive"))
      (node (ref "K9") (pin "1") (pinfunction "+_1") (pintype "passive"))
    )
    (net (code "2") (name "/ADC") (class "Default")
      (node (ref "K2") (pin "10") (pinfunction "NC_2_10") (pintype "passive"))
      (node (ref "K2") (pin "3") (pinfunction "NC_1_3") (pintype "passive"))
      (node (ref "K5") (pin "10") (pinfunction "NC_2_10") (pintype "passive"))
      (node (ref "K5") (pin "3") (pinfunction "NC_1_3") (pintype "passive"))
    )
    (net (code "3") (name "/BPF_1") (class "Default")
      (node (ref "C155") (pin "1") (pinfunction "1_1") (pintype "passive"))
      (node (ref "C156") (pin "1") (pinfunction "1_1") (pintype "passive"))
      (node (ref "D29") (pin "2") (pinfunction "A_2") (pintype "passive"))
      (node (ref "D30") (pin "2") (pinfunction "A_2") (pintype "passive"))
      (node (ref "K22") (pin "12") (pinfunction "-_12") (pintype "passive"))
      (node (ref "K23") (pin "12") (pinfunction "-_12") (pintype "passive"))
    )
    (net (code "4") (name "/BPF_2") (class "Default")
      (node (ref "C153") (pin "1") (pinfunction "1_1") (pintype "passive"))
      (node (ref "C154") (pin "1") (pinfunction "1_1") (pintype "passive"))
      (node (ref "D27") (pin "2") (pinfunction "A_2") (pintype "passive"))
      (node (ref "D28") (pin "2") (pinfunction "A_2") (pintype "passive"))
      (node (ref "K20") (pin "12") (pinfunction "-_12") (pintype "passive"))
      (node (ref "K21") (pin "12") (pinfunction "-_12") (pintype "passive"))
    )
    (net (code "5") (name "/BPF_3") (class "Default")
      (node (ref "C151") (pin "1") (pinfunction "1_1") (pintype "passive"))
      (node (ref "C152") (pin "1") (pinfunction "1_1") (pintype "passive"))
      (node (ref "D25") (pin "2") (pinfunction "A_2") (pintype "passive"))
      (node (ref "D26") (pin "2") (pinfunction "A_2") (pintype "passive"))
      (node (ref "K18") (pin "12") (pinfunction "-_12") (pintype "passive"))
      (node (ref "K19") (pin "12") (pinfunction "-_12") (pintype "passive"))
    )
    (net (code "6") (name "/BPF_4") (class "Default")
      (node (ref "C149") (pin "1") (pinfunction "1_1") (pintype "passive"))
      (node (ref "C150") (pin "1") (pinfunction "1_1") (pintype "passive"))
      (node (ref "D22") (pin "2") (pinfunction "A_2") (pintype "passive"))
      (node (ref "D24") (pin "2") (pinfunction "A_2") (pintype "passive"))
      (node (ref "K16") (pin "12") (pinfunction "-_12") (pintype "passive"))
      (node (ref "K17") (pin "12") (pinfunction "-_12") (pintype "passive"))
    )
    (net (code "7") (name "/BPF_5") (class "Default")
      (node (ref "C147") (pin "1") (pinfunction "1_1") (pintype "passive"))
      (node (ref "C148") (pin "1") (pinfunction "1_1") (pintype "passive"))
      (node (ref "D20") (pin "2") (pinfunction "A_2") (pintype "passive"))
      (node (ref "D21") (pin "2") (pinfunction "A_2") (pintype "passive"))
      (node (ref "K14") (pin "12") (pinfunction "-_12") (pintype "passive"))
      (node (ref "K15") (pin "12") (pinfunction "-_12") (pintype "passive"))
    )
    (net (code "8") (name "/BPF_6") (class "Default")
      (node (ref "C145") (pin "1") (pinfunction "1_1") (pintype "passive"))
      (node (ref "C146") (pin "1") (pinfunction "1_1") (pintype "passive"))
      (node (ref "D17") (pin "2") (pinfunction "A_2") (pintype "passive"))
      (node (ref "D19") (pin "2") (pinfunction "A_2") (pintype "passive"))
      (node (ref "K12") (pin "12") (pinfunction "-_12") (pintype "passive"))
      (node (ref "K13") (pin "12") (pinfunction "-_12") (pintype "passive"))
    )
    (net (code "9") (name "/BPF_7") (class "Default")
      (node (ref "C143") (pin "1") (pinfunction "1_1") (pintype "passive"))
      (node (ref "C144") (pin "1") (pinfunction "1_1") (pintype "passive"))
      (node (ref "D15") (pin "2") (pinfunction "A_2") (pintype "passive"))
      (node (ref "D16") (pin "2") (pinfunction "A_2") (pintype "passive"))
      (node (ref "K10") (pin "12") (pinfunction "-_12") (pintype "passive"))
      (node (ref "K11") (pin "12") (pinfunction "-_12") (pintype "passive"))
    )
    (net (code "10") (name "/BPF_8") (class "Default")
      (node (ref "C141") (pin "1") (pinfunction "1_1") (pintype "passive"))
      (node (ref "C142") (pin "1") (pinfunction "1_1") (pintype "passive"))
      (node (ref "D13") (pin "2") (pinfunction "A_2") (pintype "passive"))
      (node (ref "D14") (pin "2") (pinfunction "A_2") (pintype "passive"))
      (node (ref "K8") (pin "12") (pinfunction "-_12") (pintype "passive"))
      (node (ref "K9") (pin "12") (pinfunction "-_12") (pintype "passive"))
    )
    (net (code "11") (name "/BPF_9") (class "Default")
      (node (ref "C139") (pin "1") (pinfunction "1_1") (pintype "passive"))
      (node (ref "C140") (pin "1") (pinfunction "1_1") (pintype "passive"))
      (node (ref "D11") (pin "2") (pinfunction "A_2") (pintype "passive"))
      (node (ref "D12") (pin "2") (pinfunction "A_2") (pintype "passive"))
      (node (ref "K6") (pin "12") (pinfunction "-_12") (pintype "passive"))
      (node (ref "K7") (pin "12") (pinfunction "-_12") (pintype "passive"))
    )
    (net (code "12") (name "/HF_AMP_OUT") (class "Default")
      (node (ref "K5") (pin "5") (pinfunction "NO_1_5") (pintype "passive"))
      (node (ref "K5") (pin "8") (pinfunction "NO_2_8") (pintype "passive"))
    )
    (net (code "13") (name "/HF_BPF_IN") (class "Default")
      (node (ref "K10") (pin "4") (pinfunction "COM_1_4") (pintype "passive"))
      (node (ref "K10") (pin "9") (pinfunction "COM_2_9") (pintype "passive"))
      (node (ref "K12") (pin "4") (pinfunction "COM_1_4") (pintype "passive"))
      (node (ref "K12") (pin "9") (pinfunction "COM_2_9") (pintype "passive"))
      (node (ref "K14") (pin "4") (pinfunction "COM_1_4") (pintype "passive"))
      (node (ref "K14") (pin "9") (pinfunction "COM_2_9") (pintype "passive"))
      (node (ref "K16") (pin "4") (pinfunction "COM_1_4") (pintype "passive"))
      (node (ref "K16") (pin "9") (pinfunction "COM_2_9") (pintype "passive"))
      (node (ref "K18") (pin "4") (pinfunction "COM_1_4") (pintype "passive"))
      (node (ref "K18") (pin "9") (pinfunction "COM_2_9") (pintype "passive"))
      (node (ref "K20") (pin "4") (pinfunction "COM_1_4") (pintype "passive"))
      (node (ref "K20") (pin "9") (pinfunction "COM_2_9") (pintype "passive"))
      (node (ref "K22") (pin "4") (pinfunction "COM_1_4") (pintype "passive"))
      (node (ref "K22") (pin "9") (pinfunction "COM_2_9") (pintype "passive"))
      (node (ref "K5") (pin "4") (pinfunction "COM_1_4") (pintype "passive"))
      (node (ref "K5") (pin "9") (pinfunction "COM_2_9") (pintype "passive"))
      (node (ref "K6") (pin "4") (pinfunction "COM_1_4") (pintype "passive"))
      (node (ref "K6") (pin "9") (pinfunction "COM_2_9") (pintype "passive"))
      (node (ref "K8") (pin "4") (pinfunction "COM_1_4") (pintype "passive"))
      (node (ref "K8") (pin "9") (pinfunction "COM_2_9") (pintype "passive"))
    )
    (net (code "14") (name "/HF_BPF_OUT") (class "Default")
      (node (ref "K11") (pin "4") (pinfunction "COM_1_4") (pintype "passive"))
      (node (ref "K11") (pin "9") (pinfunction "COM_2_9") (pintype "passive"))
      (node (ref "K13") (pin "4") (pinfunction "COM_1_4") (pintype "passive"))
      (node (ref "K13") (pin "9") (pinfunction "COM_2_9") (pintype "passive"))
      (node (ref "K15") (pin "4") (pinfunction "COM_1_4") (pintype "passive"))
      (node (ref "K15") (pin "9") (pinfunction "COM_2_9") (pintype "passive"))
      (node (ref "K17") (pin "4") (pinfunction "COM_1_4") (pintype "passive"))
      (node (ref "K17") (pin "9") (pinfunction "COM_2_9") (pintype "passive"))
      (node (ref "K19") (pin "4") (pinfunction "COM_1_4") (pintype "passive"))
      (node (ref "K19") (pin "9") (pinfunction "COM_2_9") (pintype "passive"))
      (node (ref "K21") (pin "4") (pinfunction "COM_1_4") (pintype "passive"))
      (node (ref "K21") (pin "9") (pinfunction "COM_2_9") (pintype "passive"))
      (node (ref "K23") (pin "4") (pinfunction "COM_1_4") (pintype "passive"))
      (node (ref "K23") (pin "9") (pinfunction "COM_2_9") (pintype "passive"))
      (node (ref "K7") (pin "4") (pinfunction "COM_1_4") (pintype "passive"))
      (node (ref "K7") (pin "9") (pinfunction "COM_2_9") (pintype "passive"))
      (node (ref "K9") (pin "4") (pinfunction "COM_1_4") (pintype "passive"))
      (node (ref "K9") (pin "9") (pinfunction "COM_2_9") (pintype "passive"))
    )
    (net (code "15") (name "/TX_PTT_OUT") (class "Default")
      (node (ref "C125") (pin "1") (pinfunction "1_1") (pintype "passive"))
      (node (ref "C138") (pin "1") (pinfunction "1_1") (pintype "passive"))
      (node (ref "D10") (pin "2") (pinfunction "A_2") (pintype "passive"))
      (node (ref "D6") (pin "2") (pinfunction "A_2") (pintype "passive"))
      (node (ref "K2") (pin "12") (pinfunction "-_12") (pintype "passive"))
      (node (ref "K5") (pin "12") (pinfunction "-_12") (pintype "passive"))
    )
    (net (code "16") (name "/VHF_AMP_OUT") (class "Default")
      (node (ref "K2") (pin "5") (pinfunction "NO_1_5") (pintype "passive"))
      (node (ref "K2") (pin "8") (pinfunction "NO_2_8") (pintype "passive"))
    )
    (net (code "17") (name "/VHF_BPF_IN") (class "Default")
      (node (ref "K2") (pin "4") (pinfunction "COM_1_4") (pintype "passive"))
      (node (ref "K2") (pin "9") (pinfunction "COM_2_9") (pintype "passive"))
      (node (ref "L1") (pin "1") (pinfunction "A_1") (pintype "passive"))
    )
    (net (code "18") (name "/VHF_BPF_OUT") (class "Default")
      (node (ref "L2") (pin "2") (pinfunction "B_2") (pintype "passive"))
    )
    (net (code "19") (name "GND") (class "Default")
      (node (ref "C1") (pin "1") (pinfunction "1_1") (pintype "passive"))
      (node (ref "C10") (pin "1") (pinfunction "1_1") (pintype "passive"))
      (node (ref "C11") (pin "1") (pinfunction "1_1") (pintype "passive"))
      (node (ref "C14") (pin "1") (pinfunction "1_1") (pintype "passive"))
      (node (ref "C15") (pin "1") (pinfunction "1_1") (pintype "passive"))
      (node (ref "C16") (pin "1") (pinfunction "1_1") (pintype "passive"))
      (node (ref "C168") (pin "2") (pinfunction "2_2") (pintype "passive"))
      (node (ref "C19") (pin "1") (pinfunction "1_1") (pintype "passive"))
      (node (ref "C20") (pin "1") (pinfunction "1_1") (pintype "passive"))
      (node (ref "C21") (pin "1") (pinfunction "1_1") (pintype "passive"))
      (node (ref "C24") (pin "1") (pinfunction "1_1") (pintype "passive"))
      (node (ref "C25") (pin "1") (pinfunction "1_1") (pintype "passive"))
      (node (ref "C26") (pin "1") (pinfunction "1_1") (pintype "passive"))
      (node (ref "C29") (pin "1") (pinfunction "1_1") (pintype "passive"))
      (node (ref "C30") (pin "1") (pinfunction "1_1") (pintype "passive"))
      (node (ref "C31") (pin "1") (pinfunction "1_1") (pintype "passive"))
      (node (ref "C34") (pin "1") (pinfunction "1_1") (pintype "passive"))
      (node (ref "C35") (pin "1") (pinfunction "1_1") (pintype "passive"))
      (node (ref "C36") (pin "1") (pinfunction "1_1") (pintype "passive"))
      (node (ref "C4") (pin "1") (pinfunction "1_1") (pintype "passive"))
      (node (ref "C40") (pin "1") (pinfunction "1_1") (pintype "passive"))
      (node (ref "C41") (pin "1") (pinfunction "1_1") (pintype "passive"))
      (node (ref "C42") (pin "1") (pinfunction "1_1") (pintype "passive"))
      (node (ref "C45") (pin "1") (pinfunction "1_1") (pintype "passive"))
      (node (ref "C46") (pin "1") (pinfunction "1_1") (pintype "passive"))
      (node (ref "C47") (pin "1") (pinfunction "1_1") (pintype "passive"))
      (node (ref "C5") (pin "1") (pinfunction "1_1") (pintype "passive"))
      (node (ref "C50") (pin "1") (pinfunction "1_1") (pintype "passive"))
      (node (ref "C51") (pin "1") (pinfunction "1_1") (pintype "passive"))
      (node (ref "C6") (pin "1") (pinfunction "1_1") (pintype "passive"))
      (node (ref "C9") (pin "1") (pinfunction "1_1") (pintype "passive"))
      (node (ref "L12") (pin "2") (pinfunction "B_2") (pintype "passive"))
      (node (ref "L15") (pin "2") (pinfunction "B_2") (pintype "passive"))
      (node (ref "L18") (pin "2") (pinfunction "B_2") (pintype "passive"))
      (node (ref "L21") (pin "2") (pinfunction "B_2") (pintype "passive"))
      (node (ref "L24") (pin "2") (pinfunction "B_2") (pintype "passive"))
      (node (ref "L27") (pin "2") (pinfunction "B_2") (pintype "passive"))
      (node (ref "L29") (pin "2") (pinfunction "B_2") (pintype "passive"))
      (node (ref "L3") (pin "2") (pinfunction "B_2") (pintype "passive"))
      (node (ref "L6") (pin "2") (pinfunction "B_2") (pintype "passive"))
      (node (ref "L9") (pin "2") (pinfunction "B_2") (pintype "passive"))
    )
    (net (code "20") (name "Net-(K6-NO_1)") (class "Default")
      (node (ref "K6") (pin "5") (pinfunction "NO_1_5") (pintype "passive"))
      (node (ref "K6") (pin "8") (pinfunction "NO_2_8") (pintype "passive"))
      (node (ref "L4") (pin "1") (pinfunction "A_1") (pintype "passive"))
    )
    (net (code "21") (name "Net-(K7-NO_1)") (class "Default")
      (node (ref "K7") (pin "5") (pinfunction "NO_1_5") (pintype "passive"))
      (node (ref "K7") (pin "8") (pinfunction "NO_2_8") (pintype "passive"))
      (node (ref "L5") (pin "2") (pinfunction "B_2") (pintype "passive"))
    )
    (net (code "22") (name "Net-(K8-NO_1)") (class "Default")
      (node (ref "K8") (pin "5") (pinfunction "NO_1_5") (pintype "passive"))
      (node (ref "K8") (pin "8") (pinfunction "NO_2_8") (pintype "passive"))
      (node (ref "L7") (pin "1") (pinfunction "A_1") (pintype "passive"))
    )
    (net (code "23") (name "Net-(K9-NO_1)") (class "Default")
      (node (ref "K9") (pin "5") (pinfunction "NO_1_5") (pintype "passive"))
      (node (ref "K9") (pin "8") (pinfunction "NO_2_8") (pintype "passive"))
      (node (ref "L8") (pin "2") (pinfunction "B_2") (pintype "passive"))
    )
    (net (code "24") (name "Net-(K10-NO_1)") (class "Default")
      (node (ref "K10") (pin "5") (pinfunction "NO_1_5") (pintype "passive"))
      (node (ref "K10") (pin "8") (pinfunction "NO_2_8") (pintype "passive"))
      (node (ref "L10") (pin "1") (pinfunction "A_1") (pintype "passive"))
    )
    (net (code "25") (name "Net-(K11-NO_1)") (class "Default")
      (node (ref "K11") (pin "5") (pinfunction "NO_1_5") (pintype "passive"))
      (node (ref "K11") (pin "8") (pinfunction "NO_2_8") (pintype "passive"))
      (node (ref "L11") (pin "2") (pinfunction "B_2") (pintype "passive"))
    )
    (net (code "26") (name "Net-(K12-NO_1)") (class "Default")
      (node (ref "K12") (pin "5") (pinfunction "NO_1_5") (pintype "passive"))
      (node (ref "K12") (pin "8") (pinfunction "NO_2_8") (pintype "passive"))
      (node (ref "L13") (pin "1") (pinfunction "A_1") (pintype "passive"))
    )
    (net (code "27") (name "Net-(K13-NO_1)") (class "Default")
      (node (ref "K13") (pin "5") (pinfunction "NO_1_5") (pintype "passive"))
      (node (ref "K13") (pin "8") (pinfunction "NO_2_8") (pintype "passive"))
      (node (ref "L14") (pin "2") (pinfunction "B_2") (pintype "passive"))
    )
    (net (code "28") (name "Net-(K14-NO_1)") (class "Default")
      (node (ref "K14") (pin "5") (pinfunction "NO_1_5") (pintype "passive"))
      (node (ref "K14") (pin "8") (pinfunction "NO_2_8") (pintype "passive"))
      (node (ref "L16") (pin "1") (pinfunction "A_1") (pintype "passive"))
    )
    (net (code "29") (name "Net-(K15-NO_1)") (class "Default")
      (node (ref "K15") (pin "5") (pinfunction "NO_1_5") (pintype "passive"))
      (node (ref "K15") (pin "8") (pinfunction "NO_2_8") (pintype "passive"))
      (node (ref "L17") (pin "2") (pinfunction "B_2") (pintype "passive"))
    )
    (net (code "30") (name "Net-(K16-NO_1)") (class "Default")
      (node (ref "K16") (pin "5") (pinfunction "NO_1_5") (pintype "passive"))
      (node (ref "K16") (pin "8") (pinfunction "NO_2_8") (pintype "passive"))
      (node (ref "L19") (pin "1") (pinfunction "A_1") (pintype "passive"))
    )
    (net (code "31") (name "Net-(K17-NO_1)") (class "Default")
      (node (ref "K17") (pin "5") (pinfunction "NO_1_5") (pintype "passive"))
      (node (ref "K17") (pin "8") (pinfunction "NO_2_8") (pintype "passive"))
      (node (ref "L20") (pin "2") (pinfunction "B_2") (pintype "passive"))
    )
    (net (code "32") (name "Net-(K18-NO_1)") (class "Default")
      (node (ref "K18") (pin "5") (pinfunction "NO_1_5") (pintype "passive"))
      (node (ref "K18") (pin "8") (pinfunction "NO_2_8") (pintype "passive"))
      (node (ref "L22") (pin "1") (pinfunction "A_1") (pintype "passive"))
    )
    (net (code "33") (name "Net-(K19-NO_1)") (class "Default")
      (node (ref "K19") (pin "5") (pinfunction "NO_1_5") (pintype "passive"))
      (node (ref "K19") (pin "8") (pinfunction "NO_2_8") (pintype "passive"))
      (node (ref "L23") (pin "2") (pinfunction "B_2") (pintype "passive"))
    )
    (net (code "34") (name "Net-(K20-NO_1)") (class "Default")
      (node (ref "K20") (pin "5") (pinfunction "NO_1_5") (pintype "passive"))
      (node (ref "K20") (pin "8") (pinfunction "NO_2_8") (pintype "passive"))
      (node (ref "L25") (pin "1") (pinfunction "A_1") (pintype "passive"))
    )
    (net (code "35") (name "Net-(K21-NO_1)") (class "Default")
      (node (ref "K21") (pin "5") (pinfunction "NO_1_5") (pintype "passive"))
      (node (ref "K21") (pin "8") (pinfunction "NO_2_8") (pintype "passive"))
      (node (ref "L26") (pin "2") (pinfunction "B_2") (pintype "passive"))
    )
    (net (code "36") (name "Net-(K22-NO_1)") (class "Default")
      (node (ref "K22") (pin "5") (pinfunction "NO_1_5") (pintype "passive"))
      (node (ref "K22") (pin "8") (pinfunction "NO_2_8") (pintype "passive"))
      (node (ref "L40") (pin "1") (pinfunction "A_1") (pintype "passive"))
    )
    (net (code "37") (name "Net-(K23-NO_1)") (class "Default")
      (node (ref "K23") (pin "5") (pinfunction "NO_1_5") (pintype "passive"))
      (node (ref "K23") (pin "8") (pinfunction "NO_2_8") (pintype "passive"))
      (node (ref "L28") (pin "2") (pinfunction "B_2") (pintype "passive"))
    )
    (net (code "38") (name "Net-(L1-B)") (class "Default")
      (node (ref "C2") (pin "2") (pinfunction "2_2") (pintype "passive"))
      (node (ref "C4") (pin "2") (pinfunction "2_2") (pintype "passive"))
      (node (ref "L1") (pin "2") (pinfunction "B_2") (pintype "passive"))
    )
    (net (code "39") (name "Net-(L2-A)") (class "Default")
      (node (ref "C3") (pin "1") (pinfunction "1_1") (pintype "passive"))
      (node (ref "C6") (pin "2") (pinfunction "2_2") (pintype "passive"))
      (node (ref "L2") (pin "1") (pinfunction "A_1") (pintype "passive"))
    )
    (net (code "40") (name "Net-(L3-A)") (class "Default")
      (node (ref "C2") (pin "1") (pinfunction "1_1") (pintype "passive"))
      (node (ref "C3") (pin "2") (pinfunction "2_2") (pintype "passive"))
      (node (ref "C5") (pin "2") (pinfunction "2_2") (pintype "passive"))
      (node (ref "L3") (pin "1") (pinfunction "A_1") (pintype "passive"))
    )
    (net (code "41") (name "Net-(L4-B)") (class "Default")
      (node (ref "C7") (pin "2") (pinfunction "2_2") (pintype "passive"))
      (node (ref "C9") (pin "2") (pinfunction "2_2") (pintype "passive"))
      (node (ref "L4") (pin "2") (pinfunction "B_2") (pintype "passive"))
    )
    (net (code "42") (name "Net-(L5-A)") (class "Default")
      (node (ref "C11") (pin "2") (pinfunction "2_2") (pintype "passive"))
      (node (ref "C8") (pin "1") (pinfunction "1_1") (pintype "passive"))
      (node (ref "L5") (pin "1") (pinfunction "A_1") (pintype "passive"))
    )
    (net (code "43") (name "Net-(L6-A)") (class "Default")
      (node (ref "C10") (pin "2") (pinfunction "2_2") (pintype "passive"))
      (node (ref "C7") (pin "1") (pinfunction "1_1") (pintype "passive"))
      (node (ref "C8") (pin "2") (pinfunction "2_2") (pintype "passive"))
      (node (ref "L6") (pin "1") (pinfunction "A_1") (pintype "passive"))
    )
    (net (code "44") (name "Net-(L7-B)") (class "Default")
      (node (ref "C12") (pin "2") (pinfunction "2_2") (pintype "passive"))
      (node (ref "C14") (pin "2") (pinfunction "2_2") (pintype "passive"))
      (node (ref "L7") (pin "2") (pinfunction "B_2") (pintype "passive"))
    )
    (net (code "45") (name "Net-(L8-A)") (class "Default")
      (node (ref "C13") (pin "1") (pinfunction "1_1") (pintype "passive"))
      (node (ref "C16") (pin "2") (pinfunction "2_2") (pintype "passive"))
      (node (ref "L8") (pin "1") (pinfunction "A_1") (pintype "passive"))
    )
    (net (code "46") (name "Net-(L9-A)") (class "Default")
      (node (ref "C12") (pin "1") (pinfunction "1_1") (pintype "passive"))
      (node (ref "C13") (pin "2") (pinfunction "2_2") (pintype "passive"))
      (node (ref "C15") (pin "2") (pinfunction "2_2") (pintype "passive"))
      (node (ref "L9") (pin "1") (pinfunction "A_1") (pintype "passive"))
    )
    (net (code "47") (name "Net-(L10-B)") (class "Default")
      (node (ref "C17") (pin "2") (pinfunction "2_2") (pintype "passive"))
      (node (ref "C19") (pin "2") (pinfunction "2_2") (pintype "passive"))
      (node (ref "L10") (pin "2") (pinfunction "B_2") (pintype "passive"))
    )
    (net (code "48") (name "Net-(L11-A)") (class "Default")
      (node (ref "C18") (pin "1") (pinfunction "1_1") (pintype "passive"))
      (node (ref "C21") (pin "2") (pinfunction "2_2") (pintype "passive"))
      (node (ref "L11") (pin "1") (pinfunction "A_1") (pintype "passive"))
    )
    (net (code "49") (name "Net-(L12-A)") (class "Default")
      (node (ref "C17") (pin "1") (pinfunction "1_1") (pintype "passive"))
      (node (ref "C18") (pin "2") (pinfunction "2_2") (pintype "passive"))
      (node (ref "C20") (pin "2") (pinfunction "2_2") (pintype "passive"))
      (node (ref "L12") (pin "1") (pinfunction "A_1") (pintype "passive"))
    )
    (net (code "50") (name "Net-(L13-B)") (class "Default")
      (node (ref "C22") (pin "2") (pinfunction "2_2") (pintype "passive"))
      (node (ref "C24") (pin "2") (pinfunction "2_2") (pintype "passive"))
      (node (ref "L13") (pin "2") (pinfunction "B_2") (pintype "passive"))
    )
    (net (code "51") (name "Net-(L14-A)") (class "Default")
      (node (ref "C23") (pin "1") (pinfunction "1_1") (pintype "passive"))
      (node (ref "C26") (pin "2") (pinfunction "2_2") (pintype "passive"))
      (node (ref "L14") (pin "1") (pinfunction "A_1") (pintype "passive"))
    )
    (net (code "52") (name "Net-(L15-A)") (class "Default")
      (node (ref "C22") (pin "1") (pinfunction "1_1") (pintype "passive"))
      (node (ref "C23") (pin "2") (pinfunction "2_2") (pintype "passive"))
      (node (ref "C25") (pin "2") (pinfunction "2_2") (pintype "passive"))
      (node (ref "L15") (pin "1") (pinfunction "A_1") (pintype "passive"))
    )
    (net (code "53") (name "Net-(L16-B)") (class "Default")
      (node (ref "C27") (pin "2") (pinfunction "2_2") (pintype "passive"))
      (node (ref "C29") (pin "2") (pinfunction "2_2") (pintype "passive"))
      (node (ref "L16") (pin "2") (pinfunction "B_2") (pintype "passive"))
    )
    (net (code "54") (name "Net-(L17-A)") (class "Default")
      (node (ref "C28") (pin "1") (pinfunction "1_1") (pintype "passive"))
      (node (ref "C31") (pin "2") (pinfunction "2_2") (pintype "passive"))
      (node (ref "L17") (pin "1") (pinfunction "A_1") (pintype "passive"))
    )
    (net (code "55") (name "Net-(L18-A)") (class "Default")
      (node (ref "C27") (pin "1") (pinfunction "1_1") (pintype "passive"))
      (node (ref "C28") (pin "2") (pinfunction "2_2") (pintype "passive"))
      (node (ref "C30") (pin "2") (pinfunction "2_2") (pintype "passive"))
      (node (ref "L18") (pin "1") (pinfunction "A_1") (pintype "passive"))
    )
    (net (code "56") (name "Net-(L19-B)") (class "Default")
      (node (ref "C32") (pin "2") (pinfunction "2_2") (pintype "passive"))
      (node (ref "C34") (pin "2") (pinfunction "2_2") (pintype "passive"))
      (node (ref "L19") (pin "2") (pinfunction "B_2") (pintype "passive"))
    )
    (net (code "57") (name "Net-(L20-A)") (class "Default")
      (node (ref "C33") (pin "1") (pinfunction "1_1") (pintype "passive"))
      (node (ref "C36") (pin "2") (pinfunction "2_2") (pintype "passive"))
      (node (ref "L20") (pin "1") (pinfunction "A_1") (pintype "passive"))
    )
    (net (code "58") (name "Net-(L21-A)") (class "Default")
      (node (ref "C32") (pin "1") (pinfunction "1_1") (pintype "passive"))
      (node (ref "C33") (pin "2") (pinfunction "2_2") (pintype "passive"))
      (node (ref "C35") (pin "2") (pinfunction "2_2") (pintype "passive"))
      (node (ref "L21") (pin "1") (pinfunction "A_1") (pintype "passive"))
    )
    (net (code "59") (name "Net-(L22-B)") (class "Default")
      (node (ref "C37") (pin "2") (pinfunction "2_2") (pintype "passive"))
      (node (ref "C40") (pin "2") (pinfunction "2_2") (pintype "passive"))
      (node (ref "L22") (pin "2") (pinfunction "B_2") (pintype "passive"))
    )
    (net (code "60") (name "Net-(L23-A)") (class "Default")
      (node (ref "C39") (pin "1") (pinfunction "1_1") (pintype "passive"))
      (node (ref "C42") (pin "2") (pinfunction "2_2") (pintype "passive"))
      (node (ref "L23") (pin "1") (pinfunction "A_1") (pintype "passive"))
    )
    (net (code "61") (name "Net-(L24-A)") (class "Default")
      (node (ref "C37") (pin "1") (pinfunction "1_1") (pintype "passive"))
      (node (ref "C39") (pin "2") (pinfunction "2_2") (pintype "passive"))
      (node (ref "C41") (pin "2") (pinfunction "2_2") (pintype "passive"))
      (node (ref "L24") (pin "1") (pinfunction "A_1") (pintype "passive"))
    )
    (net (code "62") (name "Net-(L25-B)") (class "Default")
      (node (ref "C43") (pin "2") (pinfunction "2_2") (pintype "passive"))
      (node (ref "C45") (pin "2") (pinfunction "2_2") (pintype "passive"))
      (node (ref "L25") (pin "2") (pinfunction "B_2") (pintype "passive"))
    )
    (net (code "63") (name "Net-(L26-A)") (class "Default")
      (node (ref "C44") (pin "1") (pinfunction "1_1") (pintype "passive"))
      (node (ref "C47") (pin "2") (pinfunction "2_2") (pintype "passive"))
      (node (ref "L26") (pin "1") (pinfunction "A_1") (pintype "passive"))
    )
    (net (code "64") (name "Net-(L27-A)") (class "Default")
      (node (ref "C43") (pin "1") (pinfunction "1_1") (pintype "passive"))
      (node (ref "C44") (pin "2") (pinfunction "2_2") (pintype "passive"))
      (node (ref "C46") (pin "2") (pinfunction "2_2") (pintype "passive"))
      (node (ref "L27") (pin "1") (pinfunction "A_1") (pintype "passive"))
    )
    (net (code "65") (name "Net-(L28-A)") (class "Default")
      (node (ref "C49") (pin "1") (pinfunction "1_1") (pintype "passive"))
      (node (ref "C51") (pin "2") (pinfunction "2_2") (pintype "passive"))
      (node (ref "L28") (pin "1") (pinfunction "A_1") (pintype "passive"))
    )
    (net (code "66") (name "Net-(L29-A)") (class "Default")
      (node (ref "C48") (pin "1") (pinfunction "1_1") (pintype "passive"))
      (node (ref "C49") (pin "2") (pinfunction "2_2") (pintype "passive"))
      (node (ref "C50") (pin "2") (pinfunction "2_2") (pintype "passive"))
      (node (ref "L29") (pin "1") (pinfunction "A_1") (pintype "passive"))
    )
    (net (code "67") (name "Net-(L40-B)") (class "Default")
      (node (ref "C1") (pin "2") (pinfunction "2_2") (pintype "passive"))
      (node (ref "C48") (pin "2") (pinfunction "2_2") (pintype "passive"))
      (node (ref "L40") (pin "2") (pinfunction "B_2") (pintype "passive"))
    )
    (net (code "68") (name "unconnected-(K6-NC_1-Pad3)") (class "Default")
      (node (ref "K6") (pin "3") (pinfunction "NC_1_3") (pintype "passive"))
    )
    (net (code "69") (name "unconnected-(K6-NC_2-Pad10)") (class "Default")
      (node (ref "K6") (pin "10") (pinfunction "NC_2_10") (pintype "passive"))
    )
    (net (code "70") (name "unconnected-(K7-NC_1-Pad3)") (class "Default")
      (node (ref "K7") (pin "3") (pinfunction "NC_1_3") (pintype "passive"))
    )
    (net (code "71") (name "unconnected-(K7-NC_2-Pad10)") (class "Default")
      (node (ref "K7") (pin "10") (pinfunction "NC_2_10") (pintype "passive"))
    )
    (net (code "72") (name "unconnected-(K8-NC_1-Pad3)") (class "Default")
      (node (ref "K8") (pin "3") (pinfunction "NC_1_3") (pintype "passive"))
    )
    (net (code "73") (name "unconnected-(K8-NC_2-Pad10)") (class "Default")
      (node (ref "K8") (pin "10") (pinfunction "NC_2_10") (pintype "passive"))
    )
    (net (code "74") (name "unconnected-(K9-NC_1-Pad3)") (class "Default")
      (node (ref "K9") (pin "3") (pinfunction "NC_1_3") (pintype "passive"))
    )
    (net (code "75") (name "unconnected-(K9-NC_2-Pad10)") (class "Default")
      (node (ref "K9") (pin "10") (pinfunction "NC_2_10") (pintype "passive"))
    )
    (net (code "76") (name "unconnected-(K10-NC_1-Pad3)") (class "Default")
      (node (ref "K10") (pin "3") (pinfunction "NC_1_3") (pintype "passive"))
    )
    (net (code "77") (name "unconnected-(K10-NC_2-Pad10)") (class "Default")
      (node (ref "K10") (pin "10") (pinfunction "NC_2_10") (pintype "passive"))
    )
    (net (code "78") (name "unconnected-(K11-NC_1-Pad3)") (class "Default")
      (node (ref "K11") (pin "3") (pinfunction "NC_1_3") (pintype "passive"))
    )
    (net (code "79") (name "unconnected-(K11-NC_2-Pad10)") (class "Default")
      (node (ref "K11") (pin "10") (pinfunction "NC_2_10") (pintype "passive"))
    )
    (net (code "80") (name "unconnected-(K12-NC_1-Pad3)") (class "Default")
      (node (ref "K12") (pin "3") (pinfunction "NC_1_3") (pintype "passive"))
    )
    (net (code "81") (name "unconnected-(K12-NC_2-Pad10)") (class "Default")
      (node (ref "K12") (pin "10") (pinfunction "NC_2_10") (pintype "passive"))
    )
    (net (code "82") (name "unconnected-(K13-NC_1-Pad3)") (class "Default")
      (node (ref "K13") (pin "3") (pinfunction "NC_1_3") (pintype "passive"))
    )
    (net (code "83") (name "unconnected-(K13-NC_2-Pad10)") (class "Default")
      (node (ref "K13") (pin "10") (pinfunction "NC_2_10") (pintype "passive"))
    )
    (net (code "84") (name "unconnected-(K14-NC_1-Pad3)") (class "Default")
      (node (ref "K14") (pin "3") (pinfunction "NC_1_3") (pintype "passive"))
    )
    (net (code "85") (name "unconnected-(K14-NC_2-Pad10)") (class "Default")
      (node (ref "K14") (pin "10") (pinfunction "NC_2_10") (pintype "passive"))
    )
    (net (code "86") (name "unconnected-(K15-NC_1-Pad3)") (class "Default")
      (node (ref "K15") (pin "3") (pinfunction "NC_1_3") (pintype "passive"))
    )
    (net (code "87") (name "unconnected-(K15-NC_2-Pad10)") (class "Default")
      (node (ref "K15") (pin "10") (pinfunction "NC_2_10") (pintype "passive"))
    )
    (net (code "88") (name "unconnected-(K16-NC_1-Pad3)") (class "Default")
      (node (ref "K16") (pin "3") (pinfunction "NC_1_3") (pintype "passive"))
    )
    (net (code "89") (name "unconnected-(K16-NC_2-Pad10)") (class "Default")
      (node (ref "K16") (pin "10") (pinfunction "NC_2_10") (pintype "passive"))
    )
    (net (code "90") (name "unconnected-(K17-NC_1-Pad3)") (class "Default")
      (node (ref "K17") (pin "3") (pinfunction "NC_1_3") (pintype "passive"))
    )
    (net (code "91") (name "unconnected-(K17-NC_2-Pad10)") (class "Default")
      (node (ref "K17") (pin "10") (pinfunction "NC_2_10") (pintype "passive"))
    )
    (net (code "92") (name "unconnected-(K18-NC_1-Pad3)") (class "Default")
      (node (ref "K18") (pin "3") (pinfunction "NC_1_3") (pintype "passive"))
    )
    (net (code "93") (name "unconnected-(K18-NC_2-Pad10)") (class "Default")
      (node (ref "K18") (pin "10") (pinfunction "NC_2_10") (pintype "passive"))
    )
    (net (code "94") (name "unconnected-(K19-NC_1-Pad3)") (class "Default")
      (node (ref "K19") (pin "3") (pinfunction "NC_1_3") (pintype "passive"))
    )
    (net (code "95") (name "unconnected-(K19-NC_2-Pad10)") (class "Default")
      (node (ref "K19") (pin "10") (pinfunction "NC_2_10") (pintype "passive"))
    )
    (net (code "96") (name "unconnected-(K20-NC_1-Pad3)") (class "Default")
      (node (ref "K20") (pin "3") (pinfunction "NC_1_3") (pintype "passive"))
    )
    (net (code "97") (name "unconnected-(K20-NC_2-Pad10)") (class "Default")
      (node (ref "K20") (pin "10") (pinfunction "NC_2_10") (pintype "passive"))
    )
    (net (code "98") (name "unconnected-(K21-NC_1-Pad3)") (class "Default")
      (node (ref "K21") (pin "3") (pinfunction "NC_1_3") (pintype "passive"))
    )
    (net (code "99") (name "unconnected-(K21-NC_2-Pad10)") (class "Default")
      (node (ref "K21") (pin "10") (pinfunction "NC_2_10") (pintype "passive"))
    )
    (net (code "100") (name "unconnected-(K22-NC_1-Pad3)") (class "Default")
      (node (ref "K22") (pin "3") (pinfunction "NC_1_3") (pintype "passive"))
    )
    (net (code "101") (name "unconnected-(K22-NC_2-Pad10)") (class "Default")
      (node (ref "K22") (pin "10") (pinfunction "NC_2_10") (pintype "passive"))
    )
    (net (code "102") (name "unconnected-(K23-NC_1-Pad3)") (class "Default")
      (node (ref "K23") (pin "3") (pinfunction "NC_1_3") (pintype "passive"))
    )
    (net (code "103") (name "unconnected-(K23-NC_2-Pad10)") (class "Default")
      (node (ref "K23") (pin "10") (pinfunction "NC_2_10") (pintype "passive"))
    )
  )
)
